# STM32_H103_Extension.net
KiCad netlist of a schematic drawn in EAGLE
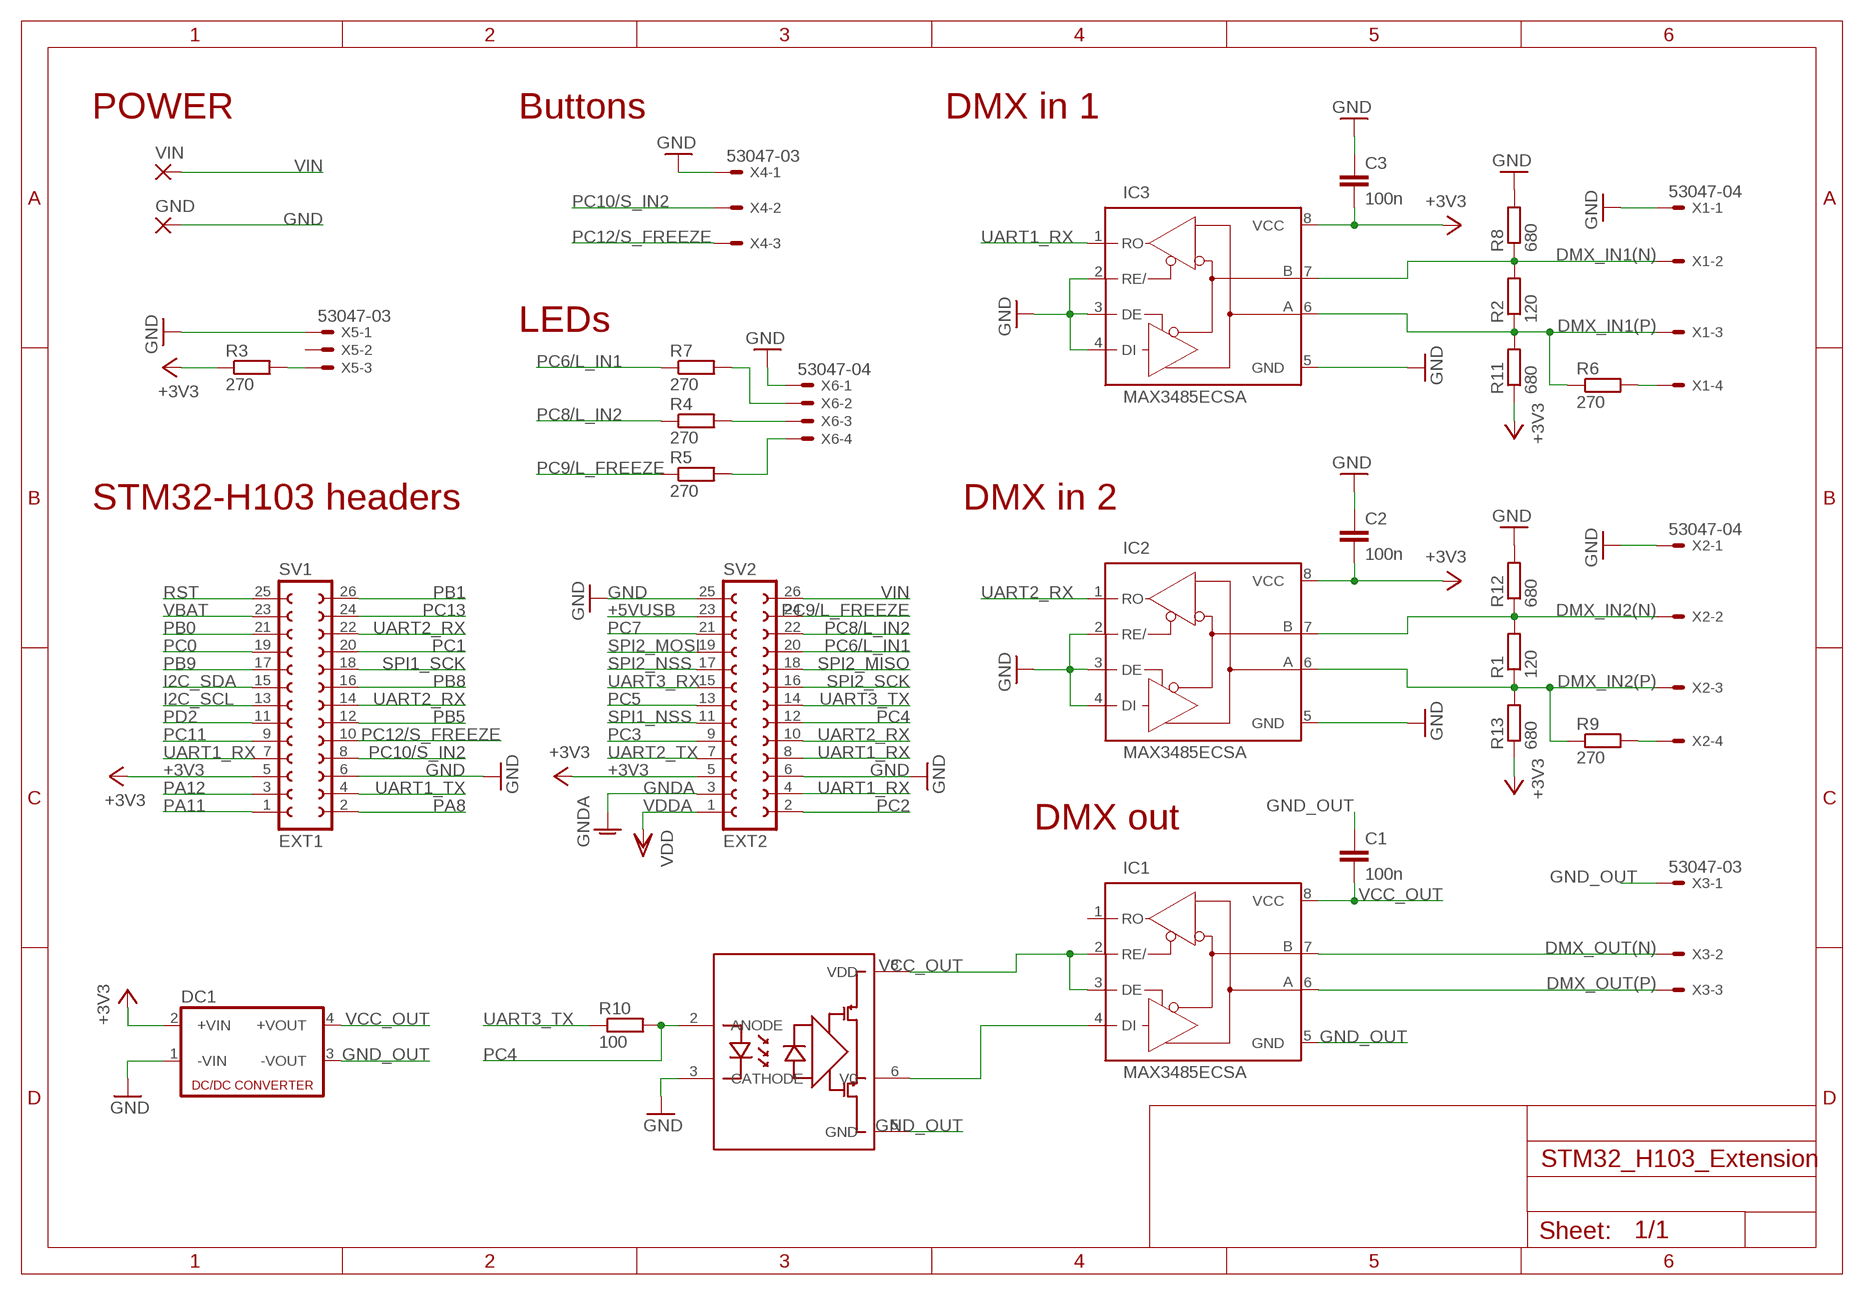
[diagram p0: schematic, sheet 1]

(export (version "E")
  (design (tool "Eeschema 10.0.6"))
  (components
    (comp (ref "C1")
      (value "100n")
      (footprint "eagle-import:C0603")
      (libsource (lib "eagle-import") (part "C-EUC0603"))
    )
    (comp (ref "C2")
      (value "100n")
      (footprint "eagle-import:C0603")
      (libsource (lib "eagle-import") (part "C-EUC0603"))
    )
    (comp (ref "C3")
      (value "100n")
      (footprint "eagle-import:C0603")
      (libsource (lib "eagle-import") (part "C-EUC0603"))
    )
    (comp (ref "DC1")
      (value "NME")
      (footprint "eagle-import:NME")
      (fields (field (name "MF") "C & D TECHNOLOGIES, INC") (field (name "MPN") "NME1205D"))
      (libsource (lib "eagle-import") (part "NME"))
    )
    (comp (ref "GND")
      (value "2,15/1,0")
      (footprint "eagle-import:2,15_1,0")
      (libsource (lib "eagle-import") (part "2,15/1,0"))
    )
    (comp (ref "IC1")
      (value "MAX3485ECSA")
      (footprint "eagle-import:SO08")
      (fields (field (name "MPN") "MAX3468ESA+T"))
      (libsource (lib "eagle-import") (part "MAX34SA68E"))
    )
    (comp (ref "IC2")
      (value "MAX3485ECSA")
      (footprint "eagle-import:SO08")
      (fields (field (name "MPN") "MAX3468ESA+T"))
      (libsource (lib "eagle-import") (part "MAX34SA68E"))
    )
    (comp (ref "IC3")
      (value "MAX3485ECSA")
      (footprint "eagle-import:SO08")
      (fields (field (name "MPN") "MAX3468ESA+T"))
      (libsource (lib "eagle-import") (part "MAX34SA68E"))
    )
    (comp (ref "R1")
      (value "120")
      (footprint "eagle-import:R0603")
      (libsource (lib "eagle-import") (part "R-EU_R0603"))
    )
    (comp (ref "R2")
      (value "120")
      (footprint "eagle-import:R0603")
      (libsource (lib "eagle-import") (part "R-EU_R0603"))
    )
    (comp (ref "R3")
      (value "270")
      (footprint "eagle-import:R0603")
      (libsource (lib "eagle-import") (part "R-EU_R0603"))
    )
    (comp (ref "R4")
      (value "270")
      (footprint "eagle-import:R0603")
      (libsource (lib "eagle-import") (part "R-EU_R0603"))
    )
    (comp (ref "R5")
      (value "270")
      (footprint "eagle-import:R0603")
      (libsource (lib "eagle-import") (part "R-EU_R0603"))
    )
    (comp (ref "R6")
      (value "270")
      (footprint "eagle-import:R0603")
      (libsource (lib "eagle-import") (part "R-EU_R0603"))
    )
    (comp (ref "R7")
      (value "270")
      (footprint "eagle-import:R0603")
      (libsource (lib "eagle-import") (part "R-EU_R0603"))
    )
    (comp (ref "R8")
      (value "680")
      (footprint "eagle-import:R0603")
      (libsource (lib "eagle-import") (part "R-EU_R0603"))
    )
    (comp (ref "R9")
      (value "270")
      (footprint "eagle-import:R0603")
      (libsource (lib "eagle-import") (part "R-EU_R0603"))
    )
    (comp (ref "R10")
      (value "100")
      (footprint "eagle-import:R0603")
      (libsource (lib "eagle-import") (part "R-EU_R0603"))
    )
    (comp (ref "R11")
      (value "680")
      (footprint "eagle-import:R0603")
      (libsource (lib "eagle-import") (part "R-EU_R0603"))
    )
    (comp (ref "R12")
      (value "680")
      (footprint "eagle-import:R0603")
      (libsource (lib "eagle-import") (part "R-EU_R0603"))
    )
    (comp (ref "R13")
      (value "680")
      (footprint "eagle-import:R0603")
      (libsource (lib "eagle-import") (part "R-EU_R0603"))
    )
    (comp (ref "SV1")
      (value "EXT1")
      (footprint "eagle-import:FE13-2")
      (libsource (lib "eagle-import") (part "FE13-2"))
    )
    (comp (ref "SV2")
      (value "EXT2")
      (footprint "eagle-import:FE13-2")
      (libsource (lib "eagle-import") (part "FE13-2"))
    )
    (comp (ref "U1")
      (value "ACPL-071L")
      (footprint "eagle-import:SOIC-8")
      (libsource (lib "eagle-import") (part "ACPL-071L"))
    )
    (comp (ref "VIN")
      (value "2,15/1,0")
      (footprint "eagle-import:2,15_1,0")
      (libsource (lib "eagle-import") (part "2,15/1,0"))
    )
    (comp (ref "X1")
      (value "53047-04")
      (footprint "eagle-import:53047-04")
      (fields (field (name "MF") "WALDOM/MOLEX") (field (name "MPN") "53047-0410"))
      (libsource (lib "eagle-import") (part "53?-04047"))
    )
    (comp (ref "X2")
      (value "53047-04")
      (footprint "eagle-import:53047-04")
      (fields (field (name "MF") "WALDOM/MOLEX") (field (name "MPN") "53047-0410"))
      (libsource (lib "eagle-import") (part "53?-04047"))
    )
    (comp (ref "X3")
      (value "53047-03")
      (footprint "eagle-import:53047-03")
      (fields (field (name "MPN") "530470310"))
      (libsource (lib "eagle-import") (part "53?-03047"))
    )
    (comp (ref "X4")
      (value "53047-03")
      (footprint "eagle-import:53047-03")
      (fields (field (name "MPN") "530470310"))
      (libsource (lib "eagle-import") (part "53?-03047"))
    )
    (comp (ref "X5")
      (value "53047-03")
      (footprint "eagle-import:53047-03")
      (fields (field (name "MPN") "530470310"))
      (libsource (lib "eagle-import") (part "53?-03047"))
    )
    (comp (ref "X6")
      (value "53047-04")
      (footprint "eagle-import:53047-04")
      (fields (field (name "MF") "WALDOM/MOLEX") (field (name "MPN") "53047-0410"))
      (libsource (lib "eagle-import") (part "53?-04047"))
    )
  )
  (nets
    (net (code "1") (name "+3V3") (class "Default")
      (node (ref "C2") (pin "2") (pinfunction "2_2") (pintype "passive"))
      (node (ref "C3") (pin "2") (pinfunction "2_2") (pintype "passive"))
      (node (ref "DC1") (pin "2") (pinfunction "+VIN_2") (pintype "passive"))
      (node (ref "IC2") (pin "8") (pinfunction "VCC_8") (pintype "power_in"))
      (node (ref "IC3") (pin "8") (pinfunction "VCC_8") (pintype "power_in"))
      (node (ref "R11") (pin "1") (pinfunction "1_1") (pintype "passive"))
      (node (ref "R13") (pin "1") (pinfunction "1_1") (pintype "passive"))
      (node (ref "R3") (pin "1") (pinfunction "1_1") (pintype "passive"))
      (node (ref "SV1") (pin "5") (pinfunction "5_5") (pintype "passive"))
      (node (ref "SV2") (pin "5") (pinfunction "5_5") (pintype "passive"))
    )
    (net (code "2") (name "/+5VUSB") (class "Default")
      (node (ref "SV2") (pin "23") (pinfunction "23_23") (pintype "passive"))
    )
    (net (code "3") (name "/DMX_IN1(N)") (class "Default")
      (node (ref "IC3") (pin "7") (pinfunction "B_7") (pintype "passive"))
      (node (ref "R2") (pin "2") (pinfunction "2_2") (pintype "passive"))
      (node (ref "R8") (pin "1") (pinfunction "1_1") (pintype "passive"))
      (node (ref "X1") (pin "2") (pinfunction "S_2") (pintype "passive"))
    )
    (net (code "4") (name "/DMX_IN1(P)") (class "Default")
      (node (ref "IC3") (pin "6") (pinfunction "A_6") (pintype "passive"))
      (node (ref "R11") (pin "2") (pinfunction "2_2") (pintype "passive"))
      (node (ref "R2") (pin "1") (pinfunction "1_1") (pintype "passive"))
      (node (ref "R6") (pin "1") (pinfunction "1_1") (pintype "passive"))
      (node (ref "X1") (pin "3") (pinfunction "S_3") (pintype "passive"))
    )
    (net (code "5") (name "/DMX_IN2(N)") (class "Default")
      (node (ref "IC2") (pin "7") (pinfunction "B_7") (pintype "passive"))
      (node (ref "R1") (pin "2") (pinfunction "2_2") (pintype "passive"))
      (node (ref "R12") (pin "1") (pinfunction "1_1") (pintype "passive"))
      (node (ref "X2") (pin "2") (pinfunction "S_2") (pintype "passive"))
    )
    (net (code "6") (name "/DMX_IN2(P)") (class "Default")
      (node (ref "IC2") (pin "6") (pinfunction "A_6") (pintype "passive"))
      (node (ref "R1") (pin "1") (pinfunction "1_1") (pintype "passive"))
      (node (ref "R13") (pin "2") (pinfunction "2_2") (pintype "passive"))
      (node (ref "R9") (pin "1") (pinfunction "1_1") (pintype "passive"))
      (node (ref "X2") (pin "3") (pinfunction "S_3") (pintype "passive"))
    )
    (net (code "7") (name "/DMX_OUT(N)") (class "Default")
      (node (ref "IC1") (pin "7") (pinfunction "B_7") (pintype "passive"))
      (node (ref "X3") (pin "2") (pinfunction "S_2") (pintype "passive"))
    )
    (net (code "8") (name "/DMX_OUT(P)") (class "Default")
      (node (ref "IC1") (pin "6") (pinfunction "A_6") (pintype "passive"))
      (node (ref "X3") (pin "3") (pinfunction "S_3") (pintype "passive"))
    )
    (net (code "9") (name "/GND_OUT") (class "Default")
      (node (ref "C1") (pin "1") (pinfunction "1_1") (pintype "passive"))
      (node (ref "DC1") (pin "3") (pinfunction "-VOUT_3") (pintype "passive"))
      (node (ref "IC1") (pin "5") (pinfunction "GND_5") (pintype "power_in"))
      (node (ref "U1") (pin "5") (pinfunction "GND_5") (pintype "power_in"))
      (node (ref "X3") (pin "1") (pinfunction "S_1") (pintype "passive"))
    )
    (net (code "10") (name "/I2C_SCL") (class "Default")
      (node (ref "SV1") (pin "13") (pinfunction "13_13") (pintype "passive"))
    )
    (net (code "11") (name "/I2C_SDA") (class "Default")
      (node (ref "SV1") (pin "15") (pinfunction "15_15") (pintype "passive"))
    )
    (net (code "12") (name "/PA8") (class "Default")
      (node (ref "SV1") (pin "2") (pinfunction "2_2") (pintype "passive"))
    )
    (net (code "13") (name "/PA11") (class "Default")
      (node (ref "SV1") (pin "1") (pinfunction "1_1") (pintype "passive"))
    )
    (net (code "14") (name "/PA12") (class "Default")
      (node (ref "SV1") (pin "3") (pinfunction "3_3") (pintype "passive"))
    )
    (net (code "15") (name "/PB0") (class "Default")
      (node (ref "SV1") (pin "21") (pinfunction "21_21") (pintype "passive"))
    )
    (net (code "16") (name "/PB1") (class "Default")
      (node (ref "SV1") (pin "26") (pinfunction "26_26") (pintype "passive"))
    )
    (net (code "17") (name "/PB5") (class "Default")
      (node (ref "SV1") (pin "12") (pinfunction "12_12") (pintype "passive"))
    )
    (net (code "18") (name "/PB8") (class "Default")
      (node (ref "SV1") (pin "16") (pinfunction "16_16") (pintype "passive"))
    )
    (net (code "19") (name "/PB9") (class "Default")
      (node (ref "SV1") (pin "17") (pinfunction "17_17") (pintype "passive"))
    )
    (net (code "20") (name "/PC0") (class "Default")
      (node (ref "SV1") (pin "19") (pinfunction "19_19") (pintype "passive"))
    )
    (net (code "21") (name "/PC1") (class "Default")
      (node (ref "SV1") (pin "20") (pinfunction "20_20") (pintype "passive"))
    )
    (net (code "22") (name "/PC2") (class "Default")
      (node (ref "SV2") (pin "2") (pinfunction "2_2") (pintype "passive"))
    )
    (net (code "23") (name "/PC3") (class "Default")
      (node (ref "SV2") (pin "9") (pinfunction "9_9") (pintype "passive"))
    )
    (net (code "24") (name "/PC4") (class "Default")
      (node (ref "R10") (pin "2") (pinfunction "2_2") (pintype "passive"))
      (node (ref "SV2") (pin "12") (pinfunction "12_12") (pintype "passive"))
      (node (ref "U1") (pin "2") (pinfunction "ANODE_2") (pintype "input"))
    )
    (net (code "25") (name "/PC5") (class "Default")
      (node (ref "SV2") (pin "13") (pinfunction "13_13") (pintype "passive"))
    )
    (net (code "26") (name "/PC6{slash}L_IN1") (class "Default")
      (node (ref "R7") (pin "1") (pinfunction "1_1") (pintype "passive"))
      (node (ref "SV2") (pin "20") (pinfunction "20_20") (pintype "passive"))
    )
    (net (code "27") (name "/PC7") (class "Default")
      (node (ref "SV2") (pin "21") (pinfunction "21_21") (pintype "passive"))
    )
    (net (code "28") (name "/PC8{slash}L_IN2") (class "Default")
      (node (ref "R4") (pin "1") (pinfunction "1_1") (pintype "passive"))
      (node (ref "SV2") (pin "22") (pinfunction "22_22") (pintype "passive"))
    )
    (net (code "29") (name "/PC9{slash}L_FREEZE") (class "Default")
      (node (ref "R5") (pin "1") (pinfunction "1_1") (pintype "passive"))
      (node (ref "SV2") (pin "24") (pinfunction "24_24") (pintype "passive"))
    )
    (net (code "30") (name "/PC10{slash}S_IN2") (class "Default")
      (node (ref "SV1") (pin "8") (pinfunction "8_8") (pintype "passive"))
      (node (ref "X4") (pin "2") (pinfunction "S_2") (pintype "passive"))
    )
    (net (code "31") (name "/PC11") (class "Default")
      (node (ref "SV1") (pin "9") (pinfunction "9_9") (pintype "passive"))
    )
    (net (code "32") (name "/PC12{slash}S_FREEZE") (class "Default")
      (node (ref "SV1") (pin "10") (pinfunction "10_10") (pintype "passive"))
      (node (ref "X4") (pin "3") (pinfunction "S_3") (pintype "passive"))
    )
    (net (code "33") (name "/PC13") (class "Default")
      (node (ref "SV1") (pin "24") (pinfunction "24_24") (pintype "passive"))
    )
    (net (code "34") (name "/PD2") (class "Default")
      (node (ref "SV1") (pin "11") (pinfunction "11_11") (pintype "passive"))
    )
    (net (code "35") (name "/RST") (class "Default")
      (node (ref "SV1") (pin "25") (pinfunction "25_25") (pintype "passive"))
    )
    (net (code "36") (name "/SPI1_NSS") (class "Default")
      (node (ref "SV2") (pin "11") (pinfunction "11_11") (pintype "passive"))
    )
    (net (code "37") (name "/SPI1_SCK") (class "Default")
      (node (ref "SV1") (pin "18") (pinfunction "18_18") (pintype "passive"))
    )
    (net (code "38") (name "/SPI2_MISO") (class "Default")
      (node (ref "SV2") (pin "18") (pinfunction "18_18") (pintype "passive"))
    )
    (net (code "39") (name "/SPI2_MOSI") (class "Default")
      (node (ref "SV2") (pin "19") (pinfunction "19_19") (pintype "passive"))
    )
    (net (code "40") (name "/SPI2_NSS") (class "Default")
      (node (ref "SV2") (pin "17") (pinfunction "17_17") (pintype "passive"))
    )
    (net (code "41") (name "/SPI2_SCK") (class "Default")
      (node (ref "SV2") (pin "16") (pinfunction "16_16") (pintype "passive"))
    )
    (net (code "42") (name "/UART1_RX") (class "Default")
      (node (ref "IC3") (pin "1") (pinfunction "RO_1") (pintype "output"))
      (node (ref "SV1") (pin "7") (pinfunction "7_7") (pintype "passive"))
      (node (ref "SV2") (pin "4") (pinfunction "4_4") (pintype "passive"))
      (node (ref "SV2") (pin "8") (pinfunction "8_8") (pintype "passive"))
    )
    (net (code "43") (name "/UART1_TX") (class "Default")
      (node (ref "SV1") (pin "4") (pinfunction "4_4") (pintype "passive"))
    )
    (net (code "44") (name "/UART2_RX") (class "Default")
      (node (ref "IC2") (pin "1") (pinfunction "RO_1") (pintype "output"))
      (node (ref "SV1") (pin "14") (pinfunction "14_14") (pintype "passive"))
      (node (ref "SV1") (pin "22") (pinfunction "22_22") (pintype "passive"))
      (node (ref "SV2") (pin "10") (pinfunction "10_10") (pintype "passive"))
    )
    (net (code "45") (name "/UART2_TX") (class "Default")
      (node (ref "SV2") (pin "7") (pinfunction "7_7") (pintype "passive"))
    )
    (net (code "46") (name "/UART3_RX") (class "Default")
      (node (ref "SV2") (pin "15") (pinfunction "15_15") (pintype "passive"))
    )
    (net (code "47") (name "/UART3_TX") (class "Default")
      (node (ref "R10") (pin "1") (pinfunction "1_1") (pintype "passive"))
      (node (ref "SV2") (pin "14") (pinfunction "14_14") (pintype "passive"))
    )
    (net (code "48") (name "/VBAT") (class "Default")
      (node (ref "SV1") (pin "23") (pinfunction "23_23") (pintype "passive"))
    )
    (net (code "49") (name "/VCC_OUT") (class "Default")
      (node (ref "C1") (pin "2") (pinfunction "2_2") (pintype "passive"))
      (node (ref "DC1") (pin "4") (pinfunction "+VOUT_4") (pintype "passive"))
      (node (ref "IC1") (pin "2") (pinfunction "RE/_2") (pintype "input"))
      (node (ref "IC1") (pin "3") (pinfunction "DE_3") (pintype "input"))
      (node (ref "IC1") (pin "8") (pinfunction "VCC_8") (pintype "power_in"))
      (node (ref "U1") (pin "8") (pinfunction "VDD_8") (pintype "power_in"))
    )
    (net (code "50") (name "/VIN") (class "Default")
      (node (ref "SV2") (pin "26") (pinfunction "26_26") (pintype "passive"))
      (node (ref "VIN") (pin "1") (pinfunction "P_1") (pintype "passive"))
    )
    (net (code "51") (name "GND") (class "Default")
      (node (ref "C2") (pin "1") (pinfunction "1_1") (pintype "passive"))
      (node (ref "C3") (pin "1") (pinfunction "1_1") (pintype "passive"))
      (node (ref "DC1") (pin "1") (pinfunction "-VIN_1") (pintype "passive"))
      (node (ref "GND") (pin "1") (pinfunction "P_1") (pintype "passive"))
      (node (ref "IC2") (pin "2") (pinfunction "RE/_2") (pintype "input"))
      (node (ref "IC2") (pin "3") (pinfunction "DE_3") (pintype "input"))
      (node (ref "IC2") (pin "4") (pinfunction "DI_4") (pintype "input"))
      (node (ref "IC2") (pin "5") (pinfunction "GND_5") (pintype "power_in"))
      (node (ref "IC3") (pin "2") (pinfunction "RE/_2") (pintype "input"))
      (node (ref "IC3") (pin "3") (pinfunction "DE_3") (pintype "input"))
      (node (ref "IC3") (pin "4") (pinfunction "DI_4") (pintype "input"))
      (node (ref "IC3") (pin "5") (pinfunction "GND_5") (pintype "power_in"))
      (node (ref "R12") (pin "2") (pinfunction "2_2") (pintype "passive"))
      (node (ref "R8") (pin "2") (pinfunction "2_2") (pintype "passive"))
      (node (ref "SV1") (pin "6") (pinfunction "6_6") (pintype "passive"))
      (node (ref "SV2") (pin "25") (pinfunction "25_25") (pintype "passive"))
      (node (ref "SV2") (pin "6") (pinfunction "6_6") (pintype "passive"))
      (node (ref "U1") (pin "3") (pinfunction "CATHODE_3") (pintype "output"))
      (node (ref "X1") (pin "1") (pinfunction "S_1") (pintype "passive"))
      (node (ref "X2") (pin "1") (pinfunction "S_1") (pintype "passive"))
      (node (ref "X4") (pin "1") (pinfunction "S_1") (pintype "passive"))
      (node (ref "X5") (pin "1") (pinfunction "S_1") (pintype "passive"))
      (node (ref "X6") (pin "1") (pinfunction "S_1") (pintype "passive"))
    )
    (net (code "52") (name "GNDA") (class "Default")
      (node (ref "SV2") (pin "3") (pinfunction "3_3") (pintype "passive"))
    )
    (net (code "53") (name "Net-(IC1-DI)") (class "Default")
      (node (ref "IC1") (pin "4") (pinfunction "DI_4") (pintype "input"))
      (node (ref "U1") (pin "6") (pinfunction "V0_6") (pintype "output"))
    )
    (net (code "54") (name "Net-(X1D-S)") (class "Default")
      (node (ref "R6") (pin "2") (pinfunction "2_2") (pintype "passive"))
      (node (ref "X1") (pin "4") (pinfunction "S_4") (pintype "passive"))
    )
    (net (code "55") (name "Net-(X2D-S)") (class "Default")
      (node (ref "R9") (pin "2") (pinfunction "2_2") (pintype "passive"))
      (node (ref "X2") (pin "4") (pinfunction "S_4") (pintype "passive"))
    )
    (net (code "56") (name "Net-(X5C-S)") (class "Default")
      (node (ref "R3") (pin "2") (pinfunction "2_2") (pintype "passive"))
      (node (ref "X5") (pin "3") (pinfunction "S_3") (pintype "passive"))
    )
    (net (code "57") (name "Net-(X6B-S)") (class "Default")
      (node (ref "R7") (pin "2") (pinfunction "2_2") (pintype "passive"))
      (node (ref "X6") (pin "2") (pinfunction "S_2") (pintype "passive"))
    )
    (net (code "58") (name "Net-(X6C-S)") (class "Default")
      (node (ref "R4") (pin "2") (pinfunction "2_2") (pintype "passive"))
      (node (ref "X6") (pin "3") (pinfunction "S_3") (pintype "passive"))
    )
    (net (code "59") (name "Net-(X6D-S)") (class "Default")
      (node (ref "R5") (pin "2") (pinfunction "2_2") (pintype "passive"))
      (node (ref "X6") (pin "4") (pinfunction "S_4") (pintype "passive"))
    )
    (net (code "60") (name "VDD") (class "Default")
      (node (ref "SV2") (pin "1") (pinfunction "1_1") (pintype "passive"))
    )
    (net (code "61") (name "unconnected-(IC1-RO-Pad1)") (class "Default")
      (node (ref "IC1") (pin "1") (pinfunction "RO_1") (pintype "output"))
    )
    (net (code "62") (name "unconnected-(X5B-S-Pad2)") (class "Default")
      (node (ref "X5") (pin "2") (pinfunction "S_2") (pintype "passive"))
    )
  )
)
